# adamon.net
KiCad netlist of a schematic drawn in EAGLE
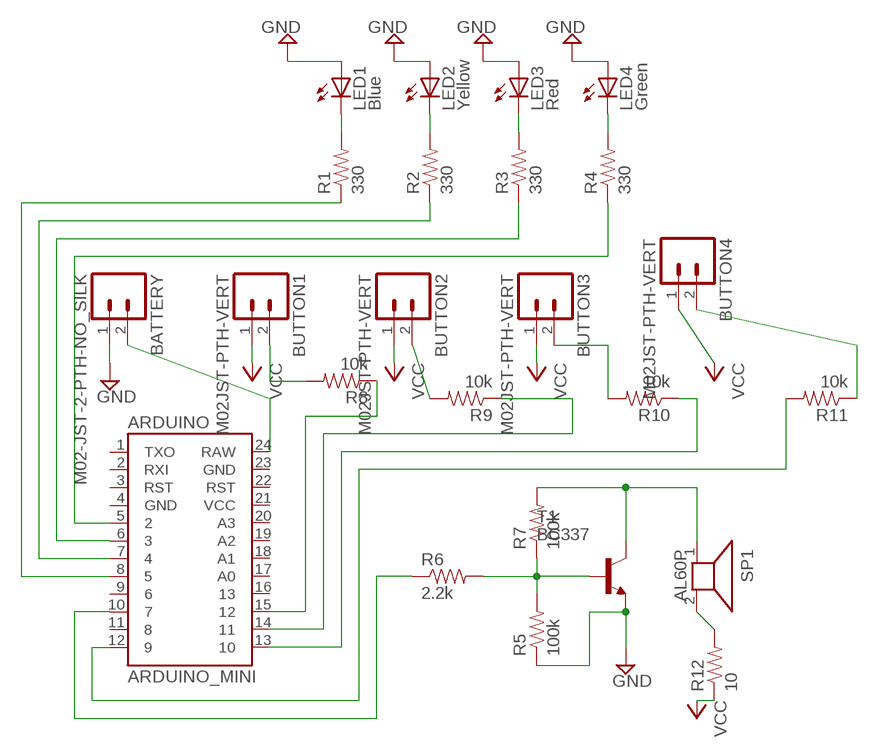
[diagram p0: schematic, sheet 1]

(export (version "E")
  (design (tool "Eeschema 10.0.6"))
  (components
    (comp (ref "ARDUINO")
      (value "ARDUINO_MINI")
      (footprint "eagle-import:ARDUINO_MINI")
      (libsource (lib "eagle-import") (part "ARDUINO_MINI"))
    )
    (comp (ref "BATTERY")
      (value "M02-JST-2-PTH-NO_SILK")
      (footprint "eagle-import:JST-2-PTH-NS")
      (libsource (lib "eagle-import") (part "M02-JST-2-PTH-NO_SILK"))
    )
    (comp (ref "BUTTON1")
      (value "M02JST-PTH-VERT")
      (footprint "eagle-import:JST-2-PTH-VERT")
      (libsource (lib "eagle-import") (part "M02JST-PTH-VERT"))
    )
    (comp (ref "BUTTON2")
      (value "M02JST-PTH-VERT")
      (footprint "eagle-import:JST-2-PTH-VERT")
      (libsource (lib "eagle-import") (part "M02JST-PTH-VERT"))
    )
    (comp (ref "BUTTON3")
      (value "M02JST-PTH-VERT")
      (footprint "eagle-import:JST-2-PTH-VERT")
      (libsource (lib "eagle-import") (part "M02JST-PTH-VERT"))
    )
    (comp (ref "BUTTON4")
      (value "M02JST-PTH-VERT")
      (footprint "eagle-import:JST-2-PTH-VERT")
      (libsource (lib "eagle-import") (part "M02JST-PTH-VERT"))
    )
    (comp (ref "LED1")
      (value "Blue")
      (footprint "eagle-import:LED5MM")
      (libsource (lib "eagle-import") (part "LED5MM"))
    )
    (comp (ref "LED2")
      (value "Yellow")
      (footprint "eagle-import:LED5MM")
      (libsource (lib "eagle-import") (part "LED5MM"))
    )
    (comp (ref "LED3")
      (value "Red")
      (footprint "eagle-import:LED5MM")
      (libsource (lib "eagle-import") (part "LED5MM"))
    )
    (comp (ref "LED4")
      (value "Green")
      (footprint "eagle-import:LED5MM")
      (libsource (lib "eagle-import") (part "LED5MM"))
    )
    (comp (ref "R1")
      (value "330")
      (footprint "eagle-import:AXIAL-0.4")
      (libsource (lib "eagle-import") (part "RESISTORPTH-1/4W"))
    )
    (comp (ref "R2")
      (value "330")
      (footprint "eagle-import:AXIAL-0.4")
      (libsource (lib "eagle-import") (part "RESISTORPTH-1/4W"))
    )
    (comp (ref "R3")
      (value "330")
      (footprint "eagle-import:AXIAL-0.4")
      (libsource (lib "eagle-import") (part "RESISTORPTH-1/4W"))
    )
    (comp (ref "R4")
      (value "330")
      (footprint "eagle-import:AXIAL-0.4")
      (libsource (lib "eagle-import") (part "RESISTORPTH-1/4W"))
    )
    (comp (ref "R5")
      (value "100k")
      (footprint "eagle-import:AXIAL-0.4")
      (libsource (lib "eagle-import") (part "RESISTORPTH-1/4W"))
    )
    (comp (ref "R6")
      (value "2.2k")
      (footprint "eagle-import:AXIAL-0.4")
      (libsource (lib "eagle-import") (part "RESISTORPTH-1/4W"))
    )
    (comp (ref "R7")
      (value "100k")
      (footprint "eagle-import:AXIAL-0.4")
      (libsource (lib "eagle-import") (part "RESISTORPTH-1/4W"))
    )
    (comp (ref "R8")
      (value "10k")
      (footprint "eagle-import:AXIAL-0.4")
      (libsource (lib "eagle-import") (part "RESISTORPTH-1/4W"))
    )
    (comp (ref "R9")
      (value "10k")
      (footprint "eagle-import:AXIAL-0.4")
      (libsource (lib "eagle-import") (part "RESISTORPTH-1/4W"))
    )
    (comp (ref "R10")
      (value "10k")
      (footprint "eagle-import:AXIAL-0.4")
      (libsource (lib "eagle-import") (part "RESISTORPTH-1/4W"))
    )
    (comp (ref "R11")
      (value "10k")
      (footprint "eagle-import:AXIAL-0.4")
      (libsource (lib "eagle-import") (part "RESISTORPTH-1/4W"))
    )
    (comp (ref "R12")
      (value "10")
      (footprint "eagle-import:AXIAL-0.4")
      (libsource (lib "eagle-import") (part "RESISTORPTH-1/4W"))
    )
    (comp (ref "SP1")
      (value "AL60P")
      (footprint "eagle-import:AL60P")
      (libsource (lib "eagle-import") (part "AL60P"))
    )
    (comp (ref "T1")
      (value "BC337")
      (footprint "eagle-import:TO92")
      (libsource (lib "eagle-import") (part "BC337"))
    )
  )
  (nets
    (net (code "1") (name "GND") (class "Default")
      (node (ref "BATTERY") (pin "1") (pinfunction "1_1") (pintype "passive"))
      (node (ref "LED1") (pin "A") (pinfunction "A_A") (pintype "passive"))
      (node (ref "LED2") (pin "A") (pinfunction "A_A") (pintype "passive"))
      (node (ref "LED3") (pin "A") (pinfunction "A_A") (pintype "passive"))
      (node (ref "LED4") (pin "A") (pinfunction "A_A") (pintype "passive"))
      (node (ref "R5") (pin "P$1") (pinfunction "1_P$1") (pintype "passive"))
      (node (ref "T1") (pin "1") (pinfunction "E_1") (pintype "passive"))
    )
    (net (code "2") (name "Net-(ARDUINO-2)") (class "Default")
      (node (ref "ARDUINO") (pin "5") (pinfunction "2_5") (pintype "bidirectional"))
      (node (ref "R4") (pin "P$1") (pinfunction "1_P$1") (pintype "passive"))
    )
    (net (code "3") (name "Net-(ARDUINO-3)") (class "Default")
      (node (ref "ARDUINO") (pin "6") (pinfunction "3_6") (pintype "bidirectional"))
      (node (ref "R3") (pin "P$1") (pinfunction "1_P$1") (pintype "passive"))
    )
    (net (code "4") (name "Net-(ARDUINO-4)") (class "Default")
      (node (ref "ARDUINO") (pin "7") (pinfunction "4_7") (pintype "bidirectional"))
      (node (ref "R2") (pin "P$1") (pinfunction "1_P$1") (pintype "passive"))
    )
    (net (code "5") (name "Net-(ARDUINO-5)") (class "Default")
      (node (ref "ARDUINO") (pin "8") (pinfunction "5_8") (pintype "bidirectional"))
      (node (ref "R1") (pin "P$1") (pinfunction "1_P$1") (pintype "passive"))
    )
    (net (code "6") (name "Net-(ARDUINO-7)") (class "Default")
      (node (ref "ARDUINO") (pin "10") (pinfunction "7_10") (pintype "bidirectional"))
      (node (ref "R6") (pin "P$1") (pinfunction "1_P$1") (pintype "passive"))
    )
    (net (code "7") (name "Net-(ARDUINO-9)") (class "Default")
      (node (ref "ARDUINO") (pin "12") (pinfunction "9_12") (pintype "bidirectional"))
      (node (ref "R11") (pin "P$2") (pinfunction "2_P$2") (pintype "passive"))
    )
    (net (code "8") (name "Net-(ARDUINO-10)") (class "Default")
      (node (ref "ARDUINO") (pin "13") (pinfunction "10_13") (pintype "bidirectional"))
      (node (ref "R10") (pin "P$1") (pinfunction "1_P$1") (pintype "passive"))
    )
    (net (code "9") (name "Net-(ARDUINO-11)") (class "Default")
      (node (ref "ARDUINO") (pin "14") (pinfunction "11_14") (pintype "bidirectional"))
      (node (ref "R9") (pin "P$1") (pinfunction "1_P$1") (pintype "passive"))
    )
    (net (code "10") (name "Net-(ARDUINO-12)") (class "Default")
      (node (ref "ARDUINO") (pin "15") (pinfunction "12_15") (pintype "bidirectional"))
      (node (ref "R8") (pin "P$1") (pinfunction "1_P$1") (pintype "passive"))
    )
    (net (code "11") (name "Net-(ARDUINO-RAW)") (class "Default")
      (node (ref "ARDUINO") (pin "24") (pinfunction "RAW_24") (pintype "bidirectional"))
      (node (ref "BATTERY") (pin "2") (pinfunction "2_2") (pintype "passive"))
    )
    (net (code "12") (name "Net-(LED1-C)") (class "Default")
      (node (ref "LED1") (pin "K") (pinfunction "C_K") (pintype "passive"))
      (node (ref "R1") (pin "P$2") (pinfunction "2_P$2") (pintype "passive"))
    )
    (net (code "13") (name "Net-(LED2-C)") (class "Default")
      (node (ref "LED2") (pin "K") (pinfunction "C_K") (pintype "passive"))
      (node (ref "R2") (pin "P$2") (pinfunction "2_P$2") (pintype "passive"))
    )
    (net (code "14") (name "Net-(LED3-C)") (class "Default")
      (node (ref "LED3") (pin "K") (pinfunction "C_K") (pintype "passive"))
      (node (ref "R3") (pin "P$2") (pinfunction "2_P$2") (pintype "passive"))
    )
    (net (code "15") (name "Net-(LED4-C)") (class "Default")
      (node (ref "LED4") (pin "K") (pinfunction "C_K") (pintype "passive"))
      (node (ref "R4") (pin "P$2") (pinfunction "2_P$2") (pintype "passive"))
    )
    (net (code "16") (name "Net-(R5-2)") (class "Default")
      (node (ref "R5") (pin "P$2") (pinfunction "2_P$2") (pintype "passive"))
      (node (ref "R6") (pin "P$2") (pinfunction "2_P$2") (pintype "passive"))
      (node (ref "R7") (pin "P$1") (pinfunction "1_P$1") (pintype "passive"))
      (node (ref "T1") (pin "2") (pinfunction "B_2") (pintype "passive"))
    )
    (net (code "17") (name "Net-(R7-2)") (class "Default")
      (node (ref "R7") (pin "P$2") (pinfunction "2_P$2") (pintype "passive"))
      (node (ref "SP1") (pin "1") (pinfunction "1_1") (pintype "passive"))
      (node (ref "T1") (pin "3") (pinfunction "C_3") (pintype "passive"))
    )
    (net (code "18") (name "Net-(R8-2)") (class "Default")
      (node (ref "BUTTON1") (pin "2") (pinfunction "2_2") (pintype "passive"))
      (node (ref "R8") (pin "P$2") (pinfunction "2_P$2") (pintype "passive"))
    )
    (net (code "19") (name "Net-(R9-2)") (class "Default")
      (node (ref "BUTTON2") (pin "2") (pinfunction "2_2") (pintype "passive"))
      (node (ref "R9") (pin "P$2") (pinfunction "2_P$2") (pintype "passive"))
    )
    (net (code "20") (name "Net-(R10-2)") (class "Default")
      (node (ref "BUTTON3") (pin "2") (pinfunction "2_2") (pintype "passive"))
      (node (ref "R10") (pin "P$2") (pinfunction "2_P$2") (pintype "passive"))
    )
    (net (code "21") (name "Net-(R11-1)") (class "Default")
      (node (ref "BUTTON4") (pin "2") (pinfunction "2_2") (pintype "passive"))
      (node (ref "R11") (pin "P$1") (pinfunction "1_P$1") (pintype "passive"))
    )
    (net (code "22") (name "Net-(R12-2)") (class "Default")
      (node (ref "R12") (pin "P$2") (pinfunction "2_P$2") (pintype "passive"))
      (node (ref "SP1") (pin "2") (pinfunction "2_2") (pintype "passive"))
    )
    (net (code "23") (name "VCC") (class "Default")
      (node (ref "BUTTON1") (pin "1") (pinfunction "1_1") (pintype "passive"))
      (node (ref "BUTTON2") (pin "1") (pinfunction "1_1") (pintype "passive"))
      (node (ref "BUTTON3") (pin "1") (pinfunction "1_1") (pintype "passive"))
      (node (ref "BUTTON4") (pin "1") (pinfunction "1_1") (pintype "passive"))
      (node (ref "R12") (pin "P$1") (pinfunction "1_P$1") (pintype "passive"))
    )
    (net (code "24") (name "unconnected-(ARDUINO-6-Pad9)") (class "Default")
      (node (ref "ARDUINO") (pin "9") (pinfunction "6_9") (pintype "bidirectional"))
    )
    (net (code "25") (name "unconnected-(ARDUINO-8-Pad11)") (class "Default")
      (node (ref "ARDUINO") (pin "11") (pinfunction "8_11") (pintype "bidirectional"))
    )
    (net (code "26") (name "unconnected-(ARDUINO-13-Pad16)") (class "Default")
      (node (ref "ARDUINO") (pin "16") (pinfunction "13_16") (pintype "bidirectional"))
    )
    (net (code "27") (name "unconnected-(ARDUINO-A0-Pad17)") (class "Default")
      (node (ref "ARDUINO") (pin "17") (pinfunction "A0_17") (pintype "bidirectional"))
    )
    (net (code "28") (name "unconnected-(ARDUINO-A1-Pad18)") (class "Default")
      (node (ref "ARDUINO") (pin "18") (pinfunction "A1_18") (pintype "bidirectional"))
    )
    (net (code "29") (name "unconnected-(ARDUINO-A2-Pad19)") (class "Default")
      (node (ref "ARDUINO") (pin "19") (pinfunction "A2_19") (pintype "bidirectional"))
    )
    (net (code "30") (name "unconnected-(ARDUINO-A3-Pad20)") (class "Default")
      (node (ref "ARDUINO") (pin "20") (pinfunction "A3_20") (pintype "bidirectional"))
    )
    (net (code "31") (name "unconnected-(ARDUINO-GND-Pad4)") (class "Default")
      (node (ref "ARDUINO") (pin "4") (pinfunction "GND_4") (pintype "bidirectional"))
    )
    (net (code "32") (name "unconnected-(ARDUINO-GND-Pad23)") (class "Default")
      (node (ref "ARDUINO") (pin "23") (pinfunction "GND_23") (pintype "bidirectional"))
    )
    (net (code "33") (name "unconnected-(ARDUINO-RST-Pad3)") (class "Default")
      (node (ref "ARDUINO") (pin "3") (pinfunction "RST_3") (pintype "bidirectional"))
    )
    (net (code "34") (name "unconnected-(ARDUINO-RST-Pad22)") (class "Default")
      (node (ref "ARDUINO") (pin "22") (pinfunction "RST_22") (pintype "bidirectional"))
    )
    (net (code "35") (name "unconnected-(ARDUINO-RXI-Pad2)") (class "Default")
      (node (ref "ARDUINO") (pin "2") (pinfunction "RXI_2") (pintype "bidirectional"))
    )
    (net (code "36") (name "unconnected-(ARDUINO-TXO-Pad1)") (class "Default")
      (node (ref "ARDUINO") (pin "1") (pinfunction "TXO_1") (pintype "bidirectional"))
    )
    (net (code "37") (name "unconnected-(ARDUINO-VCC-Pad21)") (class "Default")
      (node (ref "ARDUINO") (pin "21") (pinfunction "VCC_21") (pintype "bidirectional"))
    )
  )
)
